# nonregulation-level-shifter-mk-1_1.net
KiCad netlist of a schematic drawn in EAGLE
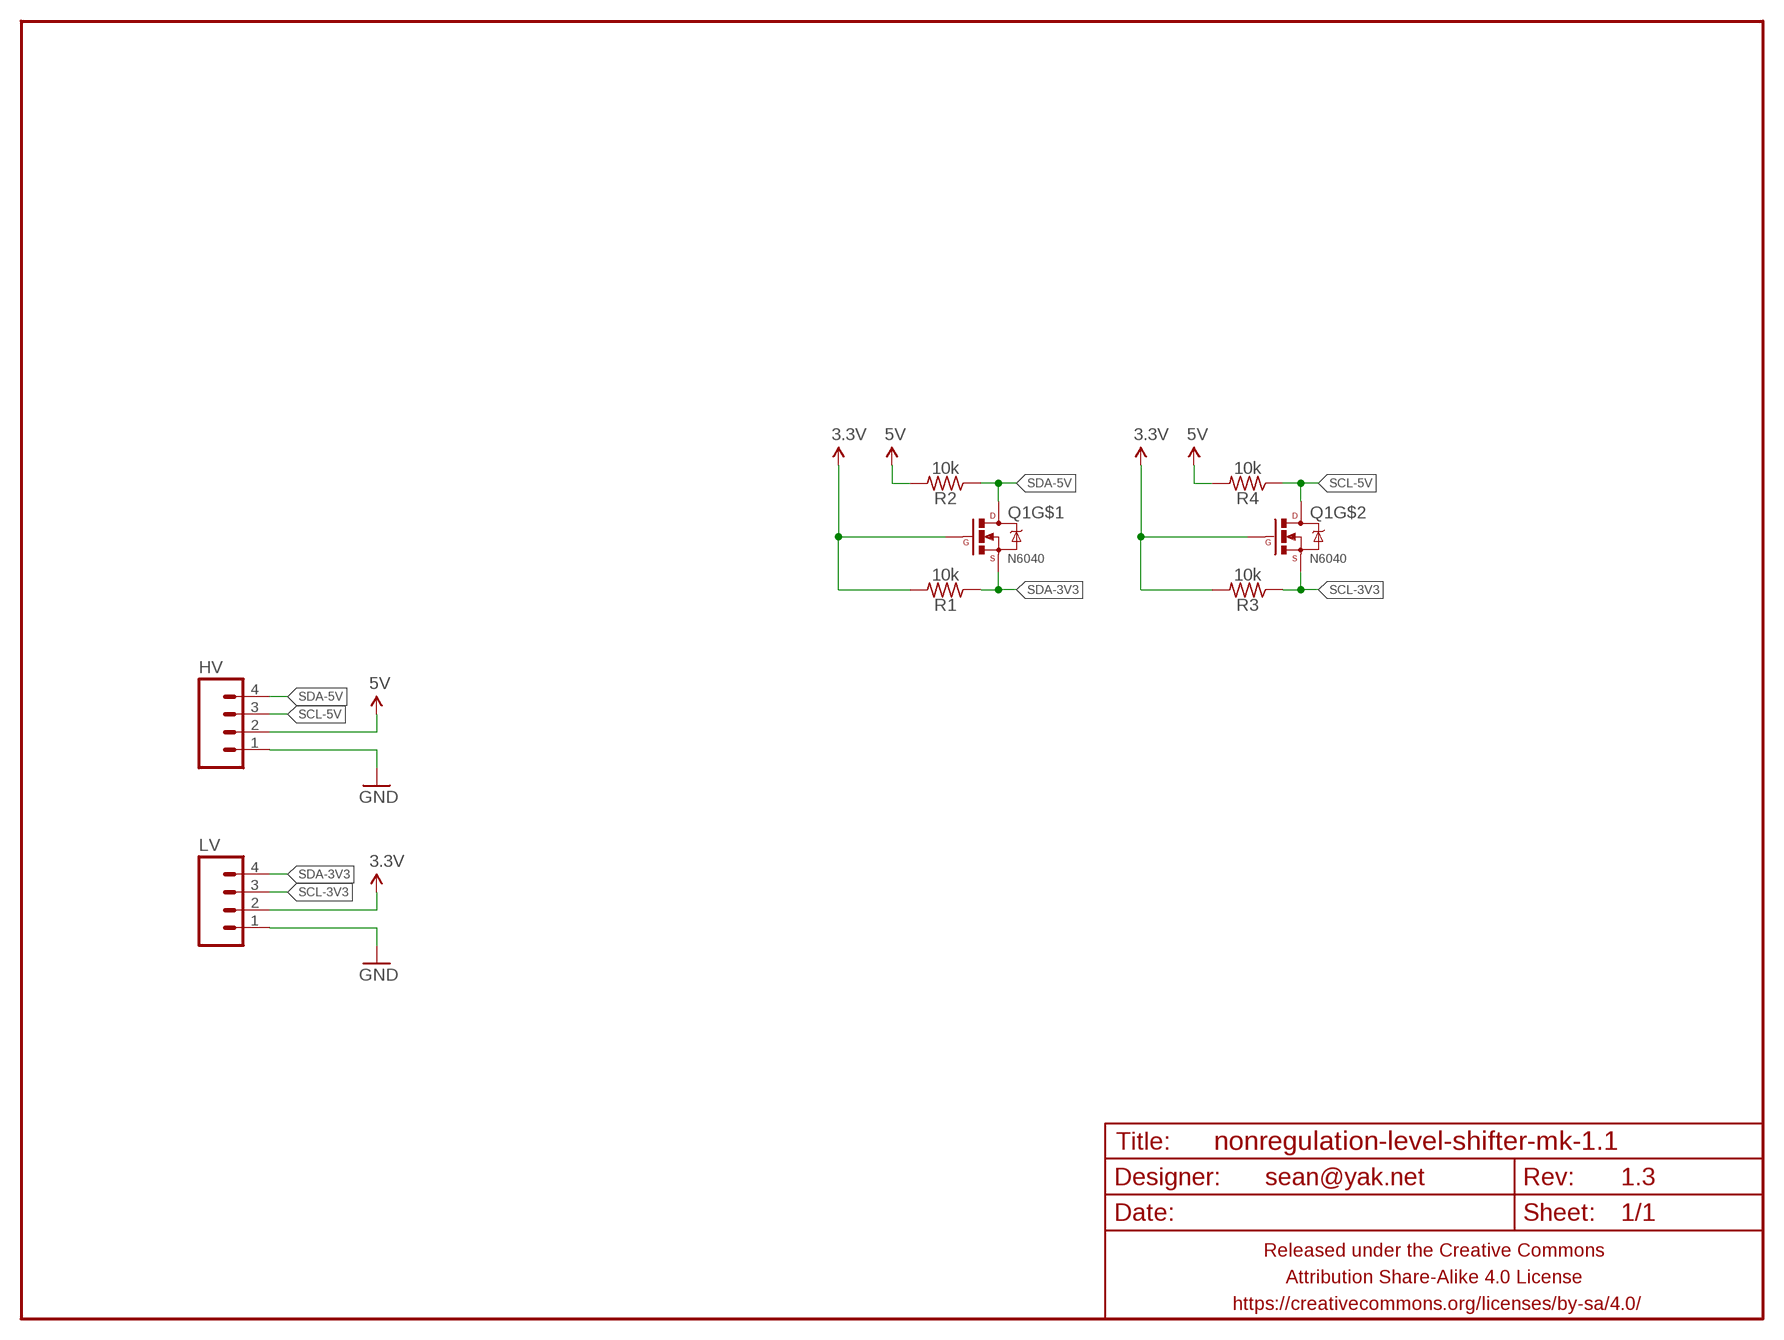
[diagram p0: schematic, sheet 1]

(export (version "E")
  (design (tool "Eeschema 10.0.6"))
  (components
    (comp (ref "FRAME1")
      (value "FRAME-LETTERNO_PACKAGE")
      (footprint "eagle-import:DUMMY")
      (fields (field (name "DESIGNER") "sean@yak.net") (field (name "VERSION") "1.3"))
      (libsource (lib "eagle-import") (part "FRAME-LETTERNO_PACKAGE"))
    )
    (comp (ref "HV")
      (value "M04PTH")
      (footprint "eagle-import:1X04-PTH-VERT")
      (libsource (lib "eagle-import") (part "M04PTH"))
    )
    (comp (ref "LV")
      (value "M04PTH")
      (footprint "eagle-import:1X04-PTH-VERT")
      (libsource (lib "eagle-import") (part "M04PTH"))
    )
    (comp (ref "Q1")
      (value "N6040")
      (footprint "eagle-import:SO08")
      (libsource (lib "eagle-import") (part "MOSFET-NCHANNEL-DUALSOIC8"))
    )
    (comp (ref "R1")
      (value "10k")
      (footprint "eagle-import:R0805")
      (libsource (lib "eagle-import") (part "RESISTORR0805"))
    )
    (comp (ref "R2")
      (value "10k")
      (footprint "eagle-import:R0805")
      (libsource (lib "eagle-import") (part "RESISTORR0805"))
    )
    (comp (ref "R3")
      (value "10k")
      (footprint "eagle-import:R0805")
      (libsource (lib "eagle-import") (part "RESISTORR0805"))
    )
    (comp (ref "R4")
      (value "10k")
      (footprint "eagle-import:R0805")
      (libsource (lib "eagle-import") (part "RESISTORR0805"))
    )
  )
  (nets
    (net (code "1") (name "3.3V") (class "Default")
      (node (ref "LV") (pin "2") (pinfunction "2_2") (pintype "passive"))
      (node (ref "Q1") (pin "2") (pinfunction "G_2") (pintype "passive"))
      (node (ref "Q1") (pin "4") (pinfunction "G_4") (pintype "passive"))
      (node (ref "R1") (pin "2") (pinfunction "2_2") (pintype "passive"))
      (node (ref "R3") (pin "2") (pinfunction "2_2") (pintype "passive"))
    )
    (net (code "2") (name "5V") (class "Default")
      (node (ref "HV") (pin "2") (pinfunction "2_2") (pintype "passive"))
      (node (ref "R2") (pin "2") (pinfunction "2_2") (pintype "passive"))
      (node (ref "R4") (pin "2") (pinfunction "2_2") (pintype "passive"))
    )
    (net (code "3") (name "GND") (class "Default")
      (node (ref "HV") (pin "1") (pinfunction "1_1") (pintype "passive"))
      (node (ref "LV") (pin "1") (pinfunction "1_1") (pintype "passive"))
    )
    (net (code "4") (name "SCL-3V3") (class "Default")
      (node (ref "LV") (pin "3") (pinfunction "3_3") (pintype "passive"))
      (node (ref "Q1") (pin "3") (pinfunction "S_3") (pintype "passive"))
      (node (ref "R3") (pin "1") (pinfunction "1_1") (pintype "passive"))
    )
    (net (code "5") (name "SCL-5V") (class "Default")
      (node (ref "HV") (pin "3") (pinfunction "3_3") (pintype "passive"))
      (node (ref "Q1") (pin "5") (pinfunction "D_5") (pintype "passive"))
      (node (ref "Q1") (pin "6") (pinfunction "D_6") (pintype "passive"))
      (node (ref "R4") (pin "1") (pinfunction "1_1") (pintype "passive"))
    )
    (net (code "6") (name "SDA-3V3") (class "Default")
      (node (ref "LV") (pin "4") (pinfunction "4_4") (pintype "passive"))
      (node (ref "Q1") (pin "1") (pinfunction "S_1") (pintype "passive"))
      (node (ref "R1") (pin "1") (pinfunction "1_1") (pintype "passive"))
    )
    (net (code "7") (name "SDA-5V") (class "Default")
      (node (ref "HV") (pin "4") (pinfunction "4_4") (pintype "passive"))
      (node (ref "Q1") (pin "7") (pinfunction "D_7") (pintype "passive"))
      (node (ref "Q1") (pin "8") (pinfunction "D_8") (pintype "passive"))
      (node (ref "R2") (pin "1") (pinfunction "1_1") (pintype "passive"))
    )
  )
)
